# MB_audio.net
KiCad netlist of a schematic drawn in Altium Designer
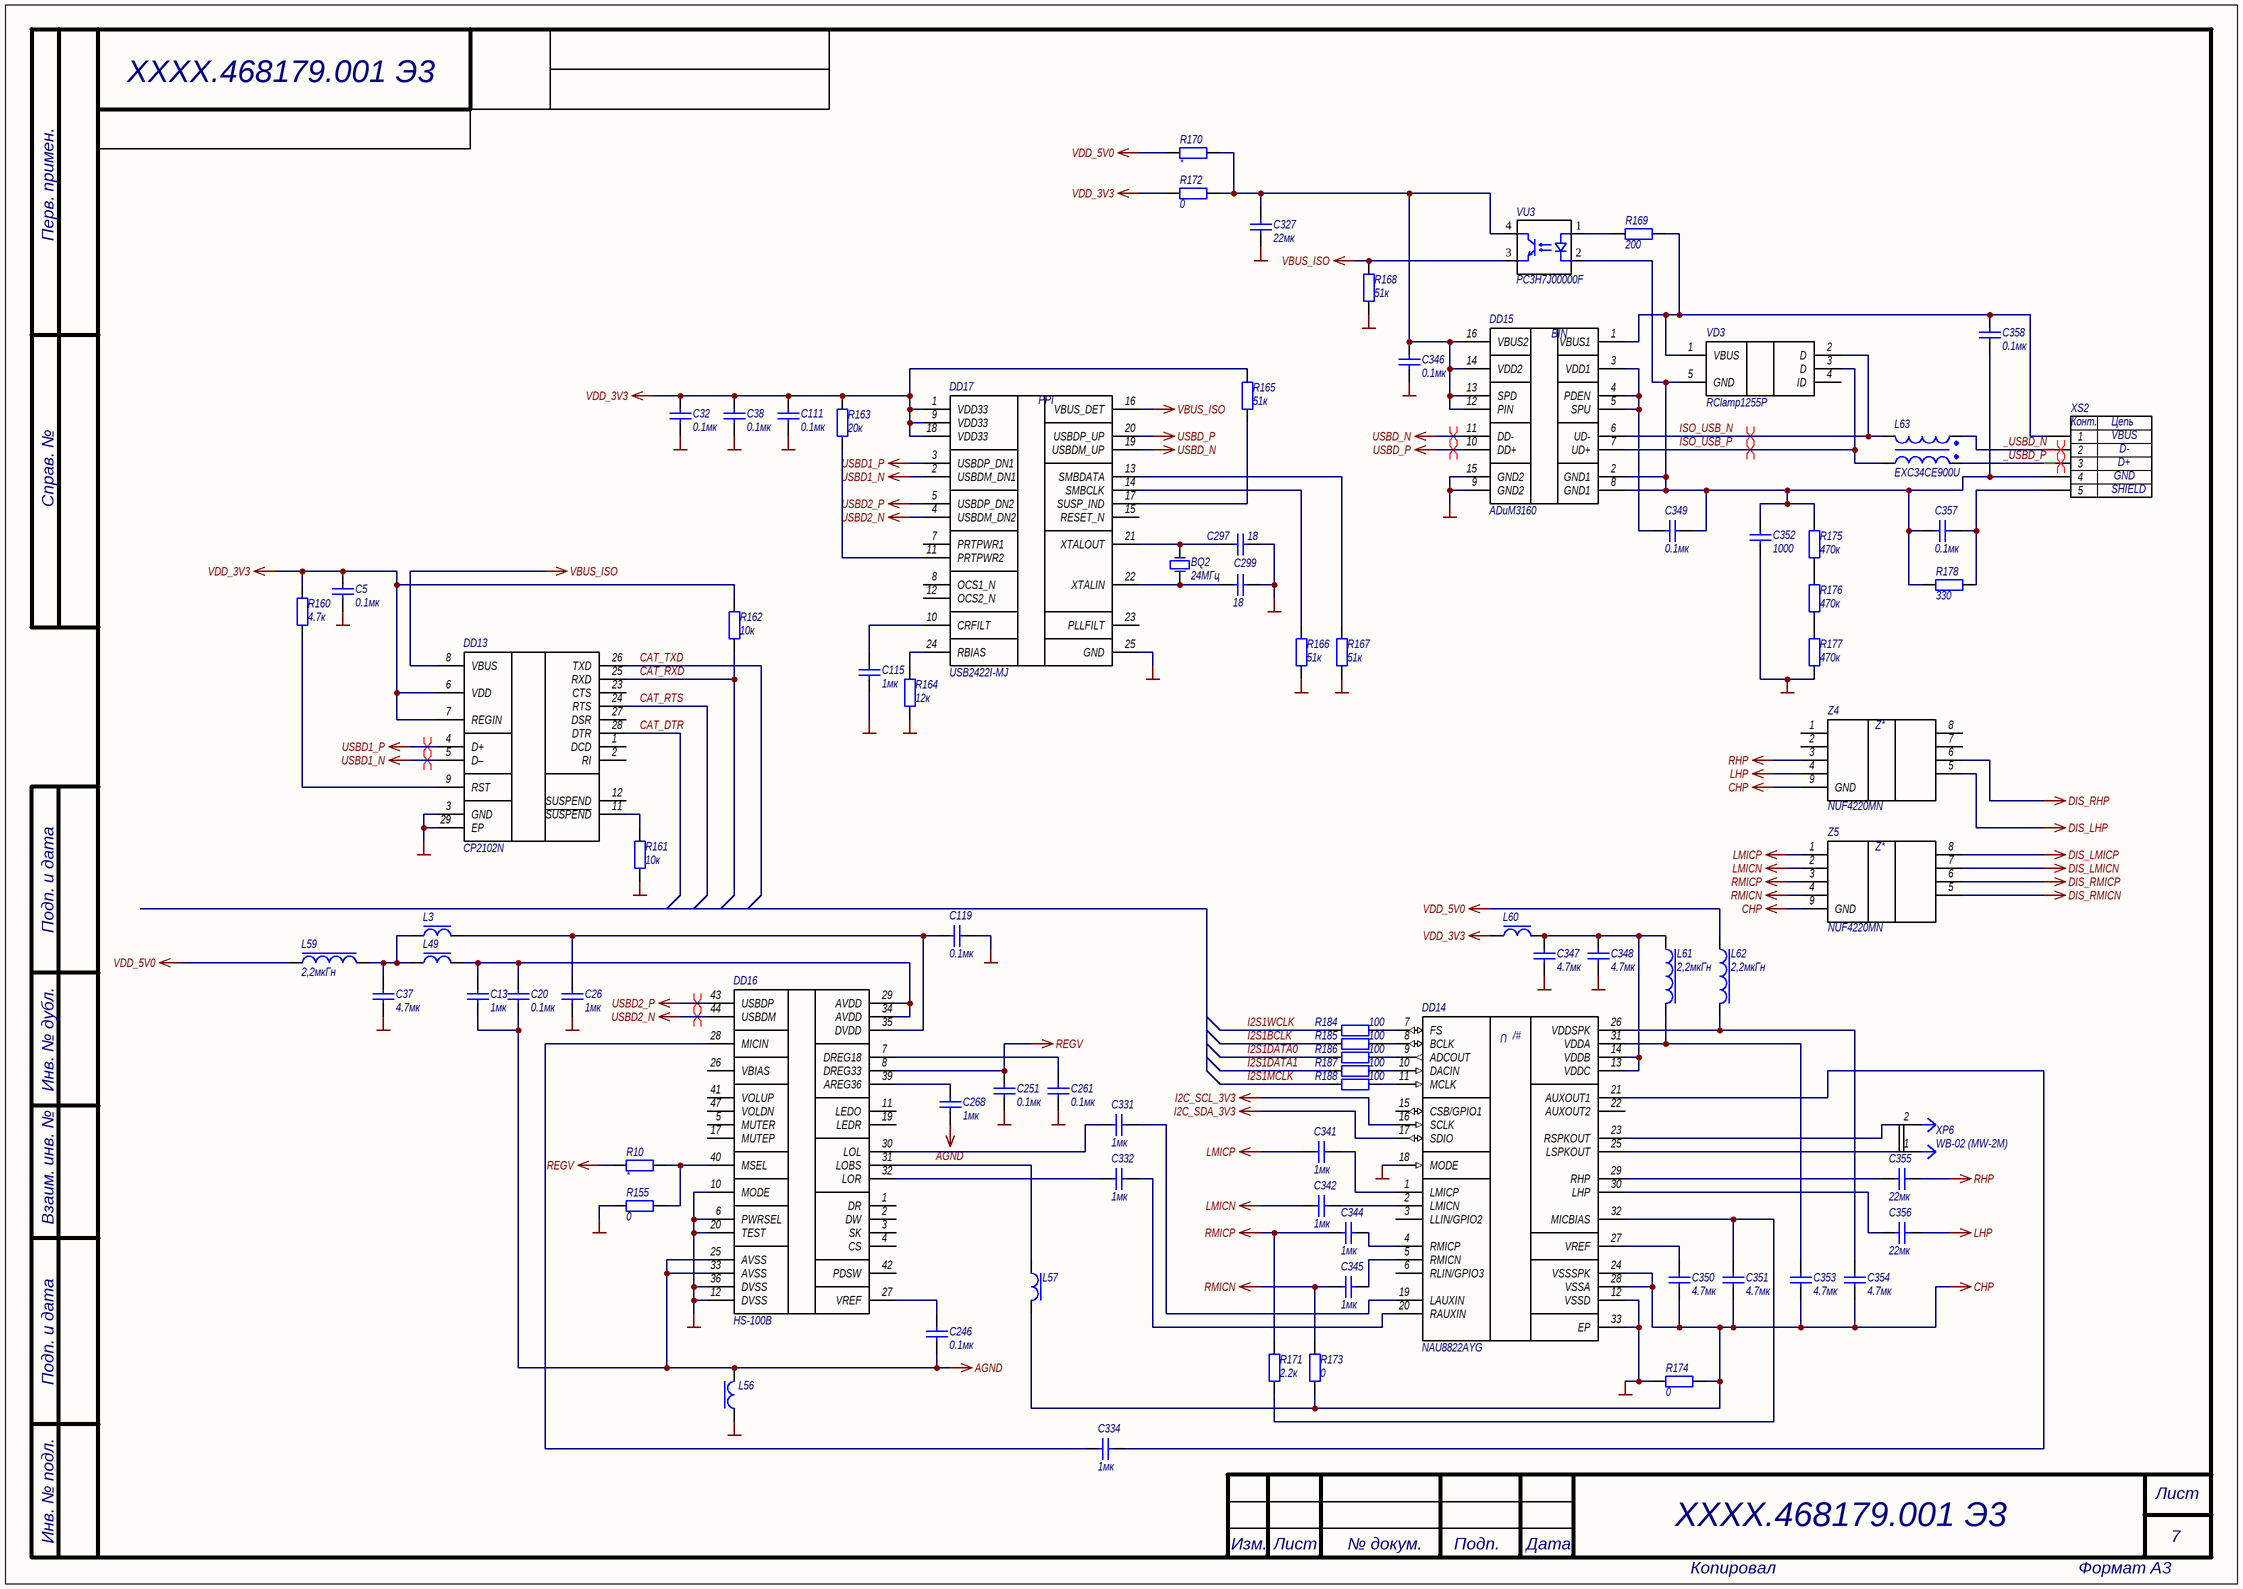
[diagram p0: MB_audio.SchDoc]

(export (version "E")
  (design (tool "Eeschema 10.0.6"))
  (components
    (comp (ref "BQ2")
      (value "24МГц")
      (footprint "ABRACOM ABM10")
      (description "Резонатор кварцевый")
      (fields (field (name "TOLERANCE") "±50 ppm") (field (name "MANUFACTURER") "ABRACON"))
      (libsource (lib "nels_other") (part "Кварц ABM10AIG-24.000MHZ-4Z-T3"))
    )
    (comp (ref "C5")
      (value "0.1мк")
      (footprint "CAPC1005X06N")
      (description "Кер. ЧИП-конденсатор")
      (fields (field (name "TOLERANCE") "±10%"))
      (libsource (lib "nels") (part "Кер.ЧИП конд. 0402 0.1мкФ X7R 10%, 16В"))
    )
    (comp (ref "C13")
      (value "1мк")
      (footprint "CAPC1005X06N")
      (description "Кер. ЧИП-конденсатор")
      (fields (field (name "TOLERANCE") "±10%"))
      (libsource (lib "nels_caps") (part "Кер.ЧИП конд. 0402 1мкФ X5R 10%, 10В"))
    )
    (comp (ref "C20")
      (value "0.1мк")
      (footprint "CAPC1005X06N")
      (description "Кер. ЧИП-конденсатор")
      (fields (field (name "TOLERANCE") "±10%"))
      (libsource (lib "nels") (part "Кер.ЧИП конд. 0402 0.1мкФ X7R 10%, 16В"))
    )
    (comp (ref "C26")
      (value "1мк")
      (footprint "CAPC1005X06N")
      (description "Кер. ЧИП-конденсатор")
      (fields (field (name "TOLERANCE") "±10%"))
      (libsource (lib "nels_caps") (part "Кер.ЧИП конд. 0402 1мкФ X5R 10%, 10В"))
    )
    (comp (ref "C32")
      (value "0.1мк")
      (footprint "CAPC1005X06N")
      (description "Кер. ЧИП-конденсатор")
      (fields (field (name "TOLERANCE") "±10%"))
      (libsource (lib "nels") (part "Кер.ЧИП конд. 0402 0.1мкФ X7R 10%, 16В"))
    )
    (comp (ref "C37")
      (value "4.7мк")
      (footprint "CAPC2012X12L")
      (description "Кер. ЧИП-конденсатор")
      (fields (field (name "TOLERANCE") "±20%") (field (name "MANUFACTURER") "Murata"))
      (libsource (lib "nels_caps") (part "Кер.ЧИП конд. 0805 4,7мкФ X5R 20% 16В"))
    )
    (comp (ref "C38")
      (value "0.1мк")
      (footprint "CAPC1005X06N")
      (description "Кер. ЧИП-конденсатор")
      (fields (field (name "TOLERANCE") "±10%"))
      (libsource (lib "nels") (part "Кер.ЧИП конд. 0402 0.1мкФ X7R 10%, 16В"))
    )
    (comp (ref "C111")
      (value "0.1мк")
      (footprint "CAPC1005X06N")
      (description "Кер. ЧИП-конденсатор")
      (fields (field (name "TOLERANCE") "±10%"))
      (libsource (lib "nels") (part "Кер.ЧИП конд. 0402 0.1мкФ X7R 10%, 16В"))
    )
    (comp (ref "C115")
      (value "1мк")
      (footprint "CAPC1005X06N")
      (description "Кер. ЧИП-конденсатор")
      (fields (field (name "TOLERANCE") "±10%"))
      (libsource (lib "nels_caps") (part "Кер.ЧИП конд. 0402 1мкФ X5R 10%, 10В"))
    )
    (comp (ref "C119")
      (value "0.1мк")
      (footprint "CAPC1005X06N")
      (description "Кер. ЧИП-конденсатор")
      (fields (field (name "TOLERANCE") "±10%"))
      (libsource (lib "nels") (part "Кер.ЧИП конд. 0402 0.1мкФ X7R 10%, 16В"))
    )
    (comp (ref "C246")
      (value "0.1мк")
      (footprint "CAPC1005X06N")
      (description "Кер. ЧИП-конденсатор")
      (fields (field (name "TOLERANCE") "±10%"))
      (libsource (lib "nels") (part "Кер.ЧИП конд. 0402 0.1мкФ X7R 10%, 16В"))
    )
    (comp (ref "C251")
      (value "0.1мк")
      (footprint "CAPC1005X06N")
      (description "Кер. ЧИП-конденсатор")
      (fields (field (name "TOLERANCE") "±10%"))
      (libsource (lib "nels") (part "Кер.ЧИП конд. 0402 0.1мкФ X7R 10%, 16В"))
    )
    (comp (ref "C261")
      (value "0.1мк")
      (footprint "CAPC1005X06N")
      (description "Кер. ЧИП-конденсатор")
      (fields (field (name "TOLERANCE") "±10%"))
      (libsource (lib "nels") (part "Кер.ЧИП конд. 0402 0.1мкФ X7R 10%, 16В"))
    )
    (comp (ref "C268")
      (value "1мк")
      (footprint "CAPC1005X06N")
      (description "Кер. ЧИП-конденсатор")
      (fields (field (name "TOLERANCE") "±10%"))
      (libsource (lib "nels_caps") (part "Кер.ЧИП конд. 0402 1мкФ X5R 10%, 10В"))
    )
    (comp (ref "C297")
      (value "18")
      (footprint "CAPC1005X06N")
      (description "Кер. ЧИП-конденсатор")
      (fields (field (name "TOLERANCE") "±5%"))
      (libsource (lib "nels_caps") (part "Кер.ЧИП конд. 0402 18пФ NPO 5%, 50В"))
    )
    (comp (ref "C299")
      (value "18")
      (footprint "CAPC1005X06N")
      (description "Кер. ЧИП-конденсатор")
      (fields (field (name "TOLERANCE") "±5%"))
      (libsource (lib "nels_caps") (part "Кер.ЧИП конд. 0402 18пФ NPO 5%, 50В"))
    )
    (comp (ref "C327")
      (value "22мк")
      (footprint "CAPC2012X12L")
      (description "Кер. ЧИП-конденсатор")
      (fields (field (name "MANUFACTURER") "TDK") (field (name "TOLERANCE") "±10%"))
      (libsource (lib "nels_caps") (part "Кер.ЧИП конд. 0805 22мкФ X5R 10% 16В"))
    )
    (comp (ref "C331")
      (value "1мк")
      (footprint "CAPC1005X06N")
      (description "Кер. ЧИП-конденсатор")
      (fields (field (name "TOLERANCE") "±10%"))
      (libsource (lib "nels_caps") (part "Кер.ЧИП конд. 0402 1мкФ X5R 10%, 10В"))
    )
    (comp (ref "C332")
      (value "1мк")
      (footprint "CAPC1005X06N")
      (description "Кер. ЧИП-конденсатор")
      (fields (field (name "TOLERANCE") "±10%"))
      (libsource (lib "nels_caps") (part "Кер.ЧИП конд. 0402 1мкФ X5R 10%, 10В"))
    )
    (comp (ref "C334")
      (value "1мк")
      (footprint "CAPC1005X06N")
      (description "Кер. ЧИП-конденсатор")
      (fields (field (name "TOLERANCE") "±10%"))
      (libsource (lib "nels_caps") (part "Кер.ЧИП конд. 0402 1мкФ X5R 10%, 10В"))
    )
    (comp (ref "C341")
      (value "1мк")
      (footprint "CAPC1005X06N")
      (description "Кер. ЧИП-конденсатор")
      (fields (field (name "TOLERANCE") "±10%"))
      (libsource (lib "nels_caps") (part "Кер.ЧИП конд. 0402 1мкФ X5R 10%, 10В"))
    )
    (comp (ref "C342")
      (value "1мк")
      (footprint "CAPC1005X06N")
      (description "Кер. ЧИП-конденсатор")
      (fields (field (name "TOLERANCE") "±10%"))
      (libsource (lib "nels_caps") (part "Кер.ЧИП конд. 0402 1мкФ X5R 10%, 10В"))
    )
    (comp (ref "C344")
      (value "1мк")
      (footprint "CAPC1005X06N")
      (description "Кер. ЧИП-конденсатор")
      (fields (field (name "TOLERANCE") "±10%"))
      (libsource (lib "nels_caps") (part "Кер.ЧИП конд. 0402 1мкФ X5R 10%, 10В"))
    )
    (comp (ref "C345")
      (value "1мк")
      (footprint "CAPC1005X06N")
      (description "Кер. ЧИП-конденсатор")
      (fields (field (name "TOLERANCE") "±10%"))
      (libsource (lib "nels_caps") (part "Кер.ЧИП конд. 0402 1мкФ X5R 10%, 10В"))
    )
    (comp (ref "C346")
      (value "0.1мк")
      (footprint "CAPC1005X06N")
      (description "Кер. ЧИП-конденсатор")
      (fields (field (name "TOLERANCE") "±10%"))
      (libsource (lib "nels") (part "Кер.ЧИП конд. 0402 0.1мкФ X7R 10%, 16В"))
    )
    (comp (ref "C347")
      (value "4.7мк")
      (footprint "CAPC2012X12L")
      (description "Кер. ЧИП-конденсатор")
      (fields (field (name "TOLERANCE") "±20%") (field (name "MANUFACTURER") "Murata"))
      (libsource (lib "nels_caps") (part "Кер.ЧИП конд. 0805 4,7мкФ X5R 20% 16В"))
    )
    (comp (ref "C348")
      (value "4.7мк")
      (footprint "CAPC2012X12L")
      (description "Кер. ЧИП-конденсатор")
      (fields (field (name "TOLERANCE") "±20%") (field (name "MANUFACTURER") "Murata"))
      (libsource (lib "nels_caps") (part "Кер.ЧИП конд. 0805 4,7мкФ X5R 20% 16В"))
    )
    (comp (ref "C349")
      (value "0.1мк")
      (footprint "CAPC1608X08L")
      (description "Кер. ЧИП-конденсатор")
      (fields (field (name "TOLERANCE") "±10%") (field (name "MANUFACTURER") "Murata"))
      (libsource (lib "nels_caps") (part "Кер.ЧИП конд. 0603 0.1мкФ X7R 10% 50В"))
    )
    (comp (ref "C350")
      (value "4.7мк")
      (footprint "CAPC2012X12L")
      (description "Кер. ЧИП-конденсатор")
      (fields (field (name "TOLERANCE") "±20%") (field (name "MANUFACTURER") "Murata"))
      (libsource (lib "nels_caps") (part "Кер.ЧИП конд. 0805 4,7мкФ X5R 20% 16В"))
    )
    (comp (ref "C351")
      (value "4.7мк")
      (footprint "CAPC2012X12L")
      (description "Кер. ЧИП-конденсатор")
      (fields (field (name "TOLERANCE") "±20%") (field (name "MANUFACTURER") "Murata"))
      (libsource (lib "nels_caps") (part "Кер.ЧИП конд. 0805 4,7мкФ X5R 20% 16В"))
    )
    (comp (ref "C352")
      (value "1000")
      (footprint "CAPRD7.5-9x5")
      (description "Защищенные конденсаторы 1000pF 250Vrms 20% L/S=10mm Bulk long")
      (fields
        (field (name "MANUFACTURER") "MURATA")
        (field (name "TOLERANCE") "±10%")
        (field (name "PUBLISHER") "Altium Limited")
      )
      (libsource (lib "nels_caps") (part "Конденсатор керамический защищенный 1000pF 250V AC (DE1E3KX102MA4BN01F)"))
    )
    (comp (ref "C353")
      (value "4.7мк")
      (footprint "CAPC2012X12L")
      (description "Кер. ЧИП-конденсатор")
      (fields (field (name "TOLERANCE") "±20%") (field (name "MANUFACTURER") "Murata"))
      (libsource (lib "nels_caps") (part "Кер.ЧИП конд. 0805 4,7мкФ X5R 20% 16В"))
    )
    (comp (ref "C354")
      (value "4.7мк")
      (footprint "CAPC2012X12L")
      (description "Кер. ЧИП-конденсатор")
      (fields (field (name "TOLERANCE") "±20%") (field (name "MANUFACTURER") "Murata"))
      (libsource (lib "nels_caps") (part "Кер.ЧИП конд. 0805 4,7мкФ X5R 20% 16В"))
    )
    (comp (ref "C355")
      (value "22мк")
      (footprint "CAPC2012X12L")
      (description "Кер. ЧИП-конденсатор")
      (fields (field (name "TOLERANCE") "±10%") (field (name "MANUFACTURER") "TDK"))
      (libsource (lib "nels_caps") (part "Кер.ЧИП конд. 0805 22мкФ X5R 10% 16В"))
    )
    (comp (ref "C356")
      (value "22мк")
      (footprint "CAPC2012X12L")
      (description "Кер. ЧИП-конденсатор")
      (fields (field (name "TOLERANCE") "±10%") (field (name "MANUFACTURER") "TDK"))
      (libsource (lib "nels_caps") (part "Кер.ЧИП конд. 0805 22мкФ X5R 10% 16В"))
    )
    (comp (ref "C357")
      (value "0.1мк")
      (footprint "CAPC1608X08L")
      (description "Кер. ЧИП-конденсатор")
      (fields (field (name "TOLERANCE") "±10%") (field (name "MANUFACTURER") "Murata"))
      (libsource (lib "nels_caps") (part "Кер.ЧИП конд. 0603 0.1мкФ X7R 10% 50В"))
    )
    (comp (ref "C358")
      (value "0.1мк")
      (footprint "CAPC1608X08L")
      (description "Кер. ЧИП-конденсатор")
      (fields (field (name "TOLERANCE") "±10%") (field (name "MANUFACTURER") "Murata"))
      (libsource (lib "nels_caps") (part "Кер.ЧИП конд. 0603 0.1мкФ X7R 10% 50В"))
    )
    (comp (ref "DD13")
      (value "CP2102N")
      (footprint "QFN50P500X500X80_HS-29N")
      (description "Single-Chip USB-to-UART Data Transfer")
      (fields (field (name "MANUFACTURER") "Silicon Labs"))
      (libsource (lib "nels_chip") (part "Микросхема CP2102N-A02-GQFN28"))
    )
    (comp (ref "DD14")
      (value "NAU8822AYG")
      (footprint "QFN50P500X500X100_HS-33L")
      (description "24-bit Stereo Audio Codec with Speaker Driver")
      (fields (field (name "MANUFACTURER") "NUVOTON"))
      (libsource (lib "nels_chip") (part "Микросхема NAU8822AYG"))
    )
    (comp (ref "DD15")
      (value "ADuM3160")
      (footprint "SOIC127P1030X265-16N")
      (description "Full/Low Speed 2.5 kV USB Digital Isolator")
      (fields (field (name "MANUFACTURER") "AD"))
      (libsource (lib "nels_chip") (part "Микросхема ADuM3160"))
    )
    (comp (ref "DD16")
      (value "HS-100B")
      (footprint "TSQFP50P900X900X160-48N")
      (description "A Highly Integrated USB Audio Single Chip")
      (fields (field (name "MANUFACTURER") "Cmedia"))
      (libsource (lib "MB") (part "Микросхема HS-100B"))
    )
    (comp (ref "DD17")
      (value "USB2422I-MJ")
      (footprint "QFN50P400X400X80_HS-25L")
      (description "2-Port USB 2.0 Hi-Speed Hub Controller")
      (fields (field (name "MANUFACTURER") "Microchip"))
      (libsource (lib "nels_chip") (part "Микросхема USB2422I-MJ"))
    )
    (comp (ref "L3")
      (value "BLM18PG121SN1D")
      (footprint "INDC1608X08L")
      (description "SMD EMI Suppression Filter EMIFIL")
      (fields (field (name "MANUFACTURER") "Murata"))
      (libsource (lib "nels_ind") (part "ЧИП дроссель 0603 BLM18PG121SN1D"))
    )
    (comp (ref "L49")
      (value "BLM18PG121SN1D")
      (footprint "INDC1608X08L")
      (description "SMD EMI Suppression Filter EMIFIL")
      (fields (field (name "MANUFACTURER") "Murata"))
      (libsource (lib "nels_ind") (part "ЧИП дроссель 0603 BLM18PG121SN1D"))
    )
    (comp (ref "L56")
      (value "BLM18PG121SN1D")
      (footprint "INDC1608X08L")
      (description "SMD EMI Suppression Filter EMIFIL")
      (fields (field (name "MANUFACTURER") "Murata"))
      (libsource (lib "nels_ind") (part "ЧИП дроссель 0603 BLM18PG121SN1D"))
    )
    (comp (ref "L57")
      (value "BLM18PG121SN1D")
      (footprint "INDC1608X08L")
      (description "SMD EMI Suppression Filter EMIFIL")
      (fields (field (name "MANUFACTURER") "Murata"))
      (libsource (lib "nels_ind") (part "ЧИП дроссель 0603 BLM18PG121SN1D"))
    )
    (comp (ref "L59")
      (value "2,2мкГн")
      (footprint "CSAB0420")
      (description "Molding Power Choke")
      (fields
        (field (name "MANUFACTURER") "Vishay")
        (field (name "MANUFACTURERPARTNUMBER") "IHLP1616ABER1R0M11")
      )
      (libsource (lib "nels_ind") (part "ЧИП индуктивность CSAB0420-2R2M"))
    )
    (comp (ref "L60")
      (value "BLM18PG121SN1D")
      (footprint "INDC1608X08L")
      (description "SMD EMI Suppression Filter EMIFIL")
      (fields (field (name "MANUFACTURER") "Murata"))
      (libsource (lib "nels_ind") (part "ЧИП дроссель 0603 BLM18PG121SN1D"))
    )
    (comp (ref "L61")
      (value "2,2мкГн")
      (footprint "CSAB0420")
      (description "Molding Power Choke")
      (fields
        (field (name "MANUFACTURER") "Vishay")
        (field (name "MANUFACTURERPARTNUMBER") "IHLP1616ABER1R0M11")
      )
      (libsource (lib "nels_ind") (part "ЧИП индуктивность CSAB0420-2R2M"))
    )
    (comp (ref "L62")
      (value "2,2мкГн")
      (footprint "CSAB0420")
      (description "Molding Power Choke")
      (fields
        (field (name "MANUFACTURER") "Vishay")
        (field (name "MANUFACTURERPARTNUMBER") "IHLP1616ABER1R0M11")
      )
      (libsource (lib "nels_ind") (part "ЧИП индуктивность CSAB0420-2R2M"))
    )
    (comp (ref "L63")
      (value "EXC34CE900U")
      (footprint "EXC34CE900U")
      (description "Common Mode Noise Filters EXC34CG/CE type")
      (fields (field (name "MANUFACTURER") "Panasonic"))
      (libsource (lib "nels_ind") (part "ЧИП синфазный фильтр 0805 EXC34CE900U"))
    )
    (comp (ref "R10")
      (value "*")
      (footprint "RESC1005X06N")
      (description "ЧИП-резистор")
      (fields (field (name "TOLERANCE") "±5%") (field (name "ALTIUM_VALUE") "*"))
      (libsource (lib "nels_res") (part "Чип резистор 0402 *"))
    )
    (comp (ref "R155")
      (value "0")
      (footprint "RESC1005X06N")
      (description "ЧИП-резистор")
      (fields (field (name "TOLERANCE") "±5%"))
      (libsource (lib "nels_res") (part "Чип резистор 0402 0 Ом"))
    )
    (comp (ref "R160")
      (value "4.7к")
      (footprint "RESC1005X06N")
      (description "ЧИП-резистор")
      (fields (field (name "TOLERANCE") "±5%"))
      (libsource (lib "nels_res") (part "Чип резистор 0402 4,7 кОм, 5%"))
    )
    (comp (ref "R161")
      (value "10к")
      (footprint "RESC1005X06N")
      (description "ЧИП-резистор")
      (fields (field (name "TOLERANCE") "±5%"))
      (libsource (lib "nels_res") (part "Чип резистор 0402 10 кОм, 5%"))
    )
    (comp (ref "R162")
      (value "10к")
      (footprint "RESC1005X06N")
      (description "ЧИП-резистор")
      (fields (field (name "TOLERANCE") "±5%"))
      (libsource (lib "nels_res") (part "Чип резистор 0402 10 кОм, 5%"))
    )
    (comp (ref "R163")
      (value "20к")
      (footprint "RESC1005X06N")
      (description "ЧИП-резистор")
      (fields (field (name "TOLERANCE") "±5%"))
      (libsource (lib "nels_res") (part "Чип резистор 0402 20 кОм, 5%"))
    )
    (comp (ref "R164")
      (value "12к")
      (footprint "RESC1005X06N")
      (description "ЧИП-резистор")
      (fields (field (name "TOLERANCE") "±5%"))
      (libsource (lib "nels_res") (part "Чип резистор 0402 12 кОм, 5%"))
    )
    (comp (ref "R165")
      (value "51к")
      (footprint "RESC1005X06N")
      (description "ЧИП-резистор")
      (fields (field (name "TOLERANCE") "±5%"))
      (libsource (lib "nels_res") (part "Чип резистор 0402 51 кОм, 5%"))
    )
    (comp (ref "R166")
      (value "51к")
      (footprint "RESC1005X06N")
      (description "ЧИП-резистор")
      (fields (field (name "TOLERANCE") "±5%"))
      (libsource (lib "nels_res") (part "Чип резистор 0402 51 кОм, 5%"))
    )
    (comp (ref "R167")
      (value "51к")
      (footprint "RESC1005X06N")
      (description "ЧИП-резистор")
      (fields (field (name "TOLERANCE") "±5%"))
      (libsource (lib "nels_res") (part "Чип резистор 0402 51 кОм, 5%"))
    )
    (comp (ref "R168")
      (value "51к")
      (footprint "RESC1005X06N")
      (description "ЧИП-резистор")
      (fields (field (name "TOLERANCE") "±5%"))
      (libsource (lib "nels_res") (part "Чип резистор 0402 51 кОм, 5%"))
    )
    (comp (ref "R169")
      (value "200")
      (footprint "RESC1005X06N")
      (description "ЧИП-резистор")
      (fields (field (name "TOLERANCE") "±5%"))
      (libsource (lib "nels_res") (part "Чип резистор 0402 200 Ом, 5%"))
    )
    (comp (ref "R170")
      (value "*")
      (footprint "RESC1005X06N")
      (description "ЧИП-резистор")
      (fields (field (name "TOLERANCE") "±5%") (field (name "ALTIUM_VALUE") "*"))
      (libsource (lib "nels_res") (part "Чип резистор 0402 *"))
    )
    (comp (ref "R171")
      (value "2.2к")
      (footprint "RESC1005X06N")
      (description "ЧИП-резистор")
      (fields (field (name "TOLERANCE") "±5%"))
      (libsource (lib "nels_res") (part "Чип резистор 0402 2,2 кОм, 5%"))
    )
    (comp (ref "R172")
      (value "0")
      (footprint "RESC1005X06N")
      (description "ЧИП-резистор")
      (fields (field (name "TOLERANCE") "±5%"))
      (libsource (lib "nels_res") (part "Чип резистор 0402 0 Ом"))
    )
    (comp (ref "R173")
      (value "0")
      (footprint "RESC1005X06N")
      (description "ЧИП-резистор")
      (fields (field (name "TOLERANCE") "±5%"))
      (libsource (lib "") (part "Чип резистор 0402 0 Ом_1"))
    )
    (comp (ref "R174")
      (value "0")
      (footprint "RESC1005X06N")
      (description "ЧИП-резистор")
      (fields (field (name "TOLERANCE") "±5%"))
      (libsource (lib "") (part "Чип резистор 0402 0 Ом_2"))
    )
    (comp (ref "R175")
      (value "470к")
      (footprint "RESC1005X06N")
      (description "ЧИП-резистор")
      (fields (field (name "TOLERANCE") "±5%"))
      (libsource (lib "nels_res") (part "Чип резистор 0402 470 кОм, 5%"))
    )
    (comp (ref "R176")
      (value "470к")
      (footprint "RESC1005X06N")
      (description "ЧИП-резистор")
      (fields (field (name "TOLERANCE") "±5%"))
      (libsource (lib "nels_res") (part "Чип резистор 0402 470 кОм, 5%"))
    )
    (comp (ref "R177")
      (value "470к")
      (footprint "RESC1005X06N")
      (description "ЧИП-резистор")
      (fields (field (name "TOLERANCE") "±5%"))
      (libsource (lib "nels_res") (part "Чип резистор 0402 470 кОм, 5%"))
    )
    (comp (ref "R178")
      (value "330")
      (footprint "RESC1005X06N")
      (description "ЧИП-резистор")
      (fields (field (name "TOLERANCE") "±5%"))
      (libsource (lib "nels_res") (part "Чип резистор 0402 330 Ом, 5%"))
    )
    (comp (ref "R184")
      (value "100")
      (footprint "RESC1005X06N")
      (description "ЧИП-резистор")
      (fields (field (name "TOLERANCE") "±5%"))
      (libsource (lib "nels_res") (part "Чип резистор 0402 100 Ом, 5%"))
    )
    (comp (ref "R185")
      (value "100")
      (footprint "RESC1005X06N")
      (description "ЧИП-резистор")
      (fields (field (name "TOLERANCE") "±5%"))
      (libsource (lib "nels_res") (part "Чип резистор 0402 100 Ом, 5%"))
    )
    (comp (ref "R186")
      (value "100")
      (footprint "RESC1005X06N")
      (description "ЧИП-резистор")
      (fields (field (name "TOLERANCE") "±5%"))
      (libsource (lib "nels_res") (part "Чип резистор 0402 100 Ом, 5%"))
    )
    (comp (ref "R187")
      (value "100")
      (footprint "RESC1005X06N")
      (description "ЧИП-резистор")
      (fields (field (name "TOLERANCE") "±5%"))
      (libsource (lib "nels_res") (part "Чип резистор 0402 100 Ом, 5%"))
    )
    (comp (ref "R188")
      (value "100")
      (footprint "RESC1005X06N")
      (description "ЧИП-резистор")
      (fields (field (name "TOLERANCE") "±5%"))
      (libsource (lib "nels_res") (part "Чип резистор 0402 100 Ом, 5%"))
    )
    (comp (ref "VD3")
      (value "RClamp1255P")
      (footprint "SLP2018P6")
      (description "Low Capacitance RClamp Surge Protection for uUSB Interfaces")
      (fields (field (name "MANUFACTURER") "SEMTECH"))
      (libsource (lib "nels_other") (part "Диодная сборка RClamp1255P"))
    )
    (comp (ref "VU3")
      (value "PC3H7J00000F")
      (footprint "SO4-170-1.27")
      (description "Mini-falt Package, General Purpose Half Pitch Photocouper")
      (libsource (lib "nels_other") (part "Оптопара транзисторная PC3H7J00000F"))
    )
    (comp (ref "XP6")
      (value "WB-02 (MW-2M)")
      (footprint "WB-02 (MW-2M) pitch 2.00mm")
      (description "Соединитель")
      (libsource (lib "nels_conn") (part "Соединитель WB-02 (MW-2M)"))
    )
    (comp (ref "XS2")
      (value "USBB-1J")
      (footprint "USB2.5-2H4D")
      (description "Universal Serial Bus (USB) Shielded I/O Receptacle, Right Angle, Type B")
      (fields (field (name "MANUFACTURER") "Connfly"))
      (libsource (lib "nels_conn") (part "Соединитель USBB-1J"))
    )
    (comp (ref "Z4")
      (value "NUF4220MN")
      (footprint "QFN50P200X200X80_HS-9L")
      (description "ESD/EMI Protection  for Audio Interfaces")
      (fields (field (name "MANUFACTURER") "onsemi"))
      (libsource (lib "nels_other") (part "Фильтр EMI NUF4220MN"))
    )
    (comp (ref "Z5")
      (value "NUF4220MN")
      (footprint "QFN50P200X200X80_HS-9L")
      (description "ESD/EMI Protection  for Audio Interfaces")
      (fields (field (name "MANUFACTURER") "onsemi"))
      (libsource (lib "nels_other") (part "Фильтр EMI NUF4220MN"))
    )
  )
  (nets
    (net (code "1") (name "/CAT_DTR") (class "Default")
      (node (ref "DD13") (pin "28") (pinfunction "DTR_28") (pintype "passive"))
    )
    (net (code "2") (name "/CAT_RTS") (class "Default")
      (node (ref "DD13") (pin "24") (pinfunction "RTS_24") (pintype "passive"))
    )
    (net (code "3") (name "/CAT_RXD") (class "Default")
      (node (ref "DD13") (pin "25") (pinfunction "RXD_25") (pintype "passive"))
      (node (ref "R162") (pin "1") (pinfunction "1_1") (pintype "passive"))
    )
    (net (code "4") (name "/CAT_TXD") (class "Default")
      (node (ref "DD13") (pin "26") (pinfunction "TXD_26") (pintype "passive"))
    )
    (net (code "5") (name "/I2S1BCLK") (class "Default")
      (node (ref "R185") (pin "1") (pinfunction "1_1") (pintype "passive"))
    )
    (net (code "6") (name "/I2S1DATA0") (class "Default")
      (node (ref "R186") (pin "1") (pinfunction "1_1") (pintype "passive"))
    )
    (net (code "7") (name "/I2S1DATA1") (class "Default")
      (node (ref "R187") (pin "1") (pinfunction "1_1") (pintype "passive"))
    )
    (net (code "8") (name "/I2S1MCLK") (class "Default")
      (node (ref "R188") (pin "1") (pinfunction "1_1") (pintype "passive"))
    )
    (net (code "9") (name "/I2S1WCLK") (class "Default")
      (node (ref "R184") (pin "1") (pinfunction "1_1") (pintype "passive"))
    )
    (net (code "10") (name "/ISO_USB_N") (class "Default")
      (node (ref "DD15") (pin "6") (pinfunction "UD-_6") (pintype "passive"))
      (node (ref "L63") (pin "2") (pinfunction "2_2") (pintype "passive"))
      (node (ref "VD3") (pin "2") (pinfunction "D_2") (pintype "passive"))
    )
    (net (code "11") (name "/ISO_USB_P") (class "Default")
      (node (ref "DD15") (pin "7") (pinfunction "UD+_7") (pintype "passive"))
      (node (ref "L63") (pin "3") (pinfunction "3_3") (pintype "passive"))
      (node (ref "VD3") (pin "3") (pinfunction "D_3") (pintype "passive"))
    )
    (net (code "12") (name "/_USBD_N") (class "Default")
      (node (ref "L63") (pin "1") (pinfunction "1_1") (pintype "passive"))
      (node (ref "XS2") (pin "2") (pinfunction "2_2") (pintype "passive"))
    )
    (net (code "13") (name "/_USBD_P") (class "Default")
      (node (ref "L63") (pin "4") (pinfunction "4_4") (pintype "passive"))
      (node (ref "XS2") (pin "3") (pinfunction "3_3") (pintype "passive"))
    )
    (net (code "14") (name "AGND") (class "Default")
      (node (ref "C13") (pin "1") (pinfunction "1_1") (pintype "passive"))
      (node (ref "C20") (pin "1") (pinfunction "1_1") (pintype "passive"))
      (node (ref "C246") (pin "1") (pinfunction "1_1") (pintype "passive"))
      (node (ref "C268") (pin "1") (pinfunction "1_1") (pintype "passive"))
      (node (ref "DD16") (pin "25") (pinfunction "AVSS_25") (pintype "passive"))
      (node (ref "DD16") (pin "33") (pinfunction "AVSS_33") (pintype "passive"))
      (node (ref "L56") (pin "2") (pinfunction "2_2") (pintype "passive"))
    )
    (net (code "15") (name "CHP") (class "Default")
      (node (ref "C350") (pin "2") (pinfunction "2_2") (pintype "passive"))
      (node (ref "C351") (pin "2") (pinfunction "2_2") (pintype "passive"))
      (node (ref "C353") (pin "2") (pinfunction "2_2") (pintype "passive"))
      (node (ref "C354") (pin "2") (pinfunction "2_2") (pintype "passive"))
      (node (ref "DD14") (pin "24") (pinfunction "VSSSPK_24") (pintype "power_in"))
      (node (ref "DD14") (pin "28") (pinfunction "VSSA_28") (pintype "power_in"))
      (node (ref "L57") (pin "2") (pinfunction "2_2") (pintype "passive"))
      (node (ref "R173") (pin "1") (pinfunction "1_1") (pintype "passive"))
      (node (ref "R174") (pin "2") (pinfunction "2_2") (pintype "passive"))
      (node (ref "Z4") (pin "9") (pinfunction "GND_9") (pintype "passive"))
      (node (ref "Z5") (pin "9") (pinfunction "GND_9") (pintype "passive"))
    )
    (net (code "16") (name "DIS_LHP") (class "Default") (node (ref "Z4") (pin "5") (pintype "passive")))
    (net (code "17") (name "DIS_LMICN") (class "Default") (node (ref "Z5") (pin "7") (pintype "passive")))
    (net (code "18") (name "DIS_LMICP") (class "Default") (node (ref "Z5") (pin "8") (pintype "passive")))
    (net (code "19") (name "DIS_RHP") (class "Default") (node (ref "Z4") (pin "6") (pintype "passive")))
    (net (code "20") (name "DIS_RMICN") (class "Default") (node (ref "Z5") (pin "5") (pintype "passive")))
    (net (code "21") (name "DIS_RMICP") (class "Default") (node (ref "Z5") (pin "6") (pintype "passive")))
    (net (code "22") (name "GND") (class "Default")
      (node (ref "C111") (pin "1") (pinfunction "1_1") (pintype "passive"))
      (node (ref "C115") (pin "1") (pinfunction "1_1") (pintype "passive"))
      (node (ref "C119") (pin "1") (pinfunction "1_1") (pintype "passive"))
      (node (ref "C251") (pin "1") (pinfunction "1_1") (pintype "passive"))
      (node (ref "C26") (pin "2") (pinfunction "2_2") (pintype "passive"))
      (node (ref "C261") (pin "1") (pinfunction "1_1") (pintype "passive"))
      (node (ref "C297") (pin "2") (pinfunction "2_2") (pintype "passive"))
      (node (ref "C299") (pin "2") (pinfunction "2_2") (pintype "passive"))
      (node (ref "C32") (pin "1") (pinfunction "1_1") (pintype "passive"))
      (node (ref "C327") (pin "1") (pinfunction "1_1") (pintype "passive"))
      (node (ref "C346") (pin "1") (pinfunction "1_1") (pintype "passive"))
      (node (ref "C347") (pin "2") (pinfunction "2_2") (pintype "passive"))
      (node (ref "C348") (pin "2") (pinfunction "2_2") (pintype "passive"))
      (node (ref "C352") (pin "2") (pinfunction "2_2") (pintype "passive"))
      (node (ref "C37") (pin "2") (pinfunction "2_2") (pintype "passive"))
      (node (ref "C38") (pin "1") (pinfunction "1_1") (pintype "passive"))
      (node (ref "C5") (pin "1") (pinfunction "1_1") (pintype "passive"))
      (node (ref "DD13") (pin "29") (pinfunction "EP_29") (pintype "passive"))
      (node (ref "DD13") (pin "3") (pinfunction "GND_3") (pintype "passive"))
      (node (ref "DD14") (pin "12") (pinfunction "VSSD_12") (pintype "power_in"))
      (node (ref "DD14") (pin "18") (pinfunction "MODE_18") (pintype "input"))
      (node (ref "DD14") (pin "33") (pinfunction "EP_33") (pintype "passive"))
      (node (ref "DD15") (pin "15") (pinfunction "GND2_15") (pintype "passive"))
      (node (ref "DD15") (pin "9") (pinfunction "GND2_9") (pintype "passive"))
      (node (ref "DD16") (pin "10") (pinfunction "MODE_10") (pintype "passive"))
      (node (ref "DD16") (pin "12") (pinfunction "DVSS_12") (pintype "passive"))
      (node (ref "DD16") (pin "20") (pinfunction "TEST_20") (pintype "passive"))
      (node (ref "DD16") (pin "36") (pinfunction "DVSS_36") (pintype "passive"))
      (node (ref "DD16") (pin "6") (pinfunction "PWRSEL_6") (pintype "passive"))
      (node (ref "DD17") (pin "25") (pinfunction "GND_25") (pintype "passive"))
      (node (ref "L56") (pin "1") (pinfunction "1_1") (pintype "passive"))
      (node (ref "R155") (pin "2") (pinfunction "2_2") (pintype "passive"))
      (node (ref "R161") (pin "1") (pinfunction "1_1") (pintype "passive"))
      (node (ref "R164") (pin "1") (pinfunction "1_1") (pintype "passive"))
      (node (ref "R166") (pin "1") (pinfunction "1_1") (pintype "passive"))
      (node (ref "R167") (pin "1") (pinfunction "1_1") (pintype "passive"))
      (node (ref "R168") (pin "1") (pinfunction "1_1") (pintype "passive"))
      (node (ref "R174") (pin "1") (pinfunction "1_1") (pintype "passive"))
      (node (ref "R177") (pin "1") (pinfunction "1_1") (pintype "passive"))
    )
    (net (code "23") (name "I2C_SCL_3V3") (class "Default")
      (node (ref "DD14") (pin "16") (pinfunction "SCLK_16") (pintype "input"))
    )
    (net (code "24") (name "I2C_SDA_3V3") (class "Default")
      (node (ref "DD14") (pin "17") (pinfunction "SDIO_17") (pintype "bidirectional"))
    )
    (net (code "25") (name "LHP") (class "Default")
      (node (ref "C356") (pin "1") (pinfunction "1_1") (pintype "passive"))
      (node (ref "Z4") (pin "4") (pintype "passive"))
    )
    (net (code "26") (name "LMICN") (class "Default")
      (node (ref "C342") (pin "1") (pinfunction "1_1") (pintype "passive"))
      (node (ref "Z5") (pin "2") (pintype "passive"))
    )
    (net (code "27") (name "LMICP") (class "Default")
      (node (ref "C341") (pin "1") (pinfunction "1_1") (pintype "passive"))
      (node (ref "Z5") (pin "1") (pintype "passive"))
    )
    (net (code "28") (name "Net-(BQ2-OSC1)") (class "Default")
      (node (ref "BQ2") (pin "1") (pinfunction "OSC1_1") (pintype "passive"))
      (node (ref "C297") (pin "1") (pinfunction "1_1") (pintype "passive"))
      (node (ref "DD17") (pin "21") (pinfunction "XTALOUT_21") (pintype "passive"))
    )
    (net (code "29") (name "Net-(BQ2-OSC2)") (class "Default")
      (node (ref "BQ2") (pin "3") (pinfunction "OSC2_3") (pintype "passive"))
      (node (ref "C299") (pin "1") (pinfunction "1_1") (pintype "passive"))
      (node (ref "DD17") (pin "22") (pinfunction "XTALIN_22") (pintype "passive"))
    )
    (net (code "30") (name "Net-(C13-Pad2)") (class "Default")
      (node (ref "C13") (pin "2") (pinfunction "2_2") (pintype "passive"))
      (node (ref "C20") (pin "2") (pinfunction "2_2") (pintype "passive"))
      (node (ref "DD16") (pin "29") (pinfunction "AVDD_29") (pintype "passive"))
      (node (ref "DD16") (pin "34") (pinfunction "AVDD_34") (pintype "passive"))
      (node (ref "L49") (pin "2") (pinfunction "2_2") (pintype "passive"))
    )
    (net (code "31") (name "Net-(C37-Pad1)") (class "Default")
      (node (ref "C37") (pin "1") (pinfunction "1_1") (pintype "passive"))
      (node (ref "L3") (pin "1") (pinfunction "1_1") (pintype "passive"))
      (node (ref "L49") (pin "1") (pinfunction "1_1") (pintype "passive"))
      (node (ref "L59") (pin "2") (pinfunction "2_2") (pintype "passive"))
    )
    (net (code "32") (name "Net-(C357-Pad1)") (class "Default")
      (node (ref "C357") (pin "1") (pinfunction "1_1") (pintype "passive"))
      (node (ref "R178") (pin "1") (pinfunction "1_1") (pintype "passive"))
      (node (ref "XS2") (pin "5") (pinfunction "5_5") (pintype "passive"))
    )
    (net (code "33") (name "Net-(DD13-RST)") (class "Default")
      (node (ref "DD13") (pin "9") (pinfunction "RST_9") (pintype "passive"))
      (node (ref "R160") (pin "1") (pinfunction "1_1") (pintype "passive"))
    )
    (net (code "34") (name "Net-(DD13-~{SUSPEND})") (class "Default")
      (node (ref "DD13") (pin "11") (pinfunction "~{SUSPEND}_11") (pintype "passive"))
      (node (ref "R161") (pin "2") (pinfunction "2_2") (pintype "passive"))
    )
    (net (code "35") (name "Net-(DD14-ADCOUT)") (class "Default")
      (node (ref "DD14") (pin "9") (pinfunction "ADCOUT_9") (pintype "output"))
      (node (ref "R186") (pin "2") (pinfunction "2_2") (pintype "passive"))
    )
    (net (code "36") (name "Net-(DD14-AUXOUT1)") (class "Default")
      (node (ref "C334") (pin "2") (pinfunction "2_2") (pintype "passive"))
      (node (ref "DD14") (pin "21") (pinfunction "AUXOUT1_21") (pintype "passive"))
    )
    (net (code "37") (name "Net-(DD14-BCLK)") (class "Default")
      (node (ref "DD14") (pin "8") (pinfunction "BCLK_8") (pintype "bidirectional"))
      (node (ref "R185") (pin "2") (pinfunction "2_2") (pintype "passive"))
    )
    (net (code "38") (name "Net-(DD14-DACIN)") (class "Default")
      (node (ref "DD14") (pin "10") (pinfunction "DACIN_10") (pintype "input"))
      (node (ref "R187") (pin "2") (pinfunction "2_2") (pintype "passive"))
    )
    (net (code "39") (name "Net-(DD14-FS)") (class "Default")
      (node (ref "DD14") (pin "7") (pinfunction "FS_7") (pintype "bidirectional"))
      (node (ref "R184") (pin "2") (pinfunction "2_2") (pintype "passive"))
    )
    (net (code "40") (name "Net-(DD14-LAUXIN)") (class "Default")
      (node (ref "C331") (pin "2") (pinfunction "2_2") (pintype "passive"))
      (node (ref "DD14") (pin "19") (pinfunction "LAUXIN_19") (pintype "passive"))
    )
    (net (code "41") (name "Net-(DD14-LHP)") (class "Default")
      (node (ref "C356") (pin "2") (pinfunction "2_2") (pintype "passive"))
      (node (ref "DD14") (pin "30") (pinfunction "LHP_30") (pintype "passive"))
    )
    (net (code "42") (name "Net-(DD14-LMICN)") (class "Default")
      (node (ref "C342") (pin "2") (pinfunction "2_2") (pintype "passive"))
      (node (ref "DD14") (pin "2") (pinfunction "LMICN_2") (pintype "passive"))
    )
    (net (code "43") (name "Net-(DD14-LMICP)") (class "Default")
      (node (ref "C341") (pin "2") (pinfunction "2_2") (pintype "passive"))
      (node (ref "DD14") (pin "1") (pinfunction "LMICP_1") (pintype "passive"))
    )
    (net (code "44") (name "Net-(DD14-LSPKOUT)") (class "Default")
      (node (ref "DD14") (pin "25") (pinfunction "LSPKOUT_25") (pintype "passive"))
      (node (ref "XP6") (pin "1") (pinfunction "~_1") (pintype "passive"))
    )
    (net (code "45") (name "Net-(DD14-MCLK)") (class "Default")
      (node (ref "DD14") (pin "11") (pinfunction "MCLK_11") (pintype "input"))
      (node (ref "R188") (pin "2") (pinfunction "2_2") (pintype "passive"))
    )
    (net (code "46") (name "Net-(DD14-MICBIAS)") (class "Default")
      (node (ref "C351") (pin "1") (pinfunction "1_1") (pintype "passive"))
      (node (ref "DD14") (pin "32") (pinfunction "MICBIAS_32") (pintype "passive"))
      (node (ref "R171") (pin "1") (pinfunction "1_1") (pintype "passive"))
    )
    (net (code "47") (name "Net-(DD14-RAUXIN)") (class "Default")
      (node (ref "C332") (pin "2") (pinfunction "2_2") (pintype "passive"))
      (node (ref "DD14") (pin "20") (pinfunction "RAUXIN_20") (pintype "passive"))
    )
    (net (code "48") (name "Net-(DD14-RHP)") (class "Default")
      (node (ref "C355") (pin "2") (pinfunction "2_2") (pintype "passive"))
      (node (ref "DD14") (pin "29") (pinfunction "RHP_29") (pintype "passive"))
    )
    (net (code "49") (name "Net-(DD14-RMICN)") (class "Default")
      (node (ref "C345") (pin "2") (pinfunction "2_2") (pintype "passive"))
      (node (ref "DD14") (pin "5") (pinfunction "RMICN_5") (pintype "passive"))
    )
    (net (code "50") (name "Net-(DD14-RMICP)") (class "Default")
      (node (ref "C344") (pin "2") (pinfunction "2_2") (pintype "passive"))
      (node (ref "DD14") (pin "4") (pinfunction "RMICP_4") (pintype "passive"))
    )
    (net (code "51") (name "Net-(DD14-RSPKOUT)") (class "Default")
      (node (ref "DD14") (pin "23") (pinfunction "RSPKOUT_23") (pintype "passive"))
      (node (ref "XP6") (pin "2") (pinfunction "~_2") (pintype "passive"))
    )
    (net (code "52") (name "Net-(DD14-VDDA)") (class "Default")
      (node (ref "C353") (pin "1") (pinfunction "1_1") (pintype "passive"))
      (node (ref "DD14") (pin "31") (pinfunction "VDDA_31") (pintype "power_in"))
      (node (ref "L61") (pin "2") (pinfunction "2_2") (pintype "passive"))
    )
    (net (code "53") (name "Net-(DD14-VDDB)") (class "Default")
      (node (ref "C347") (pin "1") (pinfunction "1_1") (pintype "passive"))
      (node (ref "C348") (pin "1") (pinfunction "1_1") (pintype "passive"))
      (node (ref "DD14") (pin "13") (pinfunction "VDDC_13") (pintype "power_in"))
      (node (ref "DD14") (pin "14") (pinfunction "VDDB_14") (pintype "power_in"))
      (node (ref "L60") (pin "2") (pinfunction "2_2") (pintype "passive"))
      (node (ref "L61") (pin "1") (pinfunction "1_1") (pintype "passive"))
    )
    (net (code "54") (name "Net-(DD14-VDDSPK)") (class "Default")
      (node (ref "C354") (pin "1") (pinfunction "1_1") (pintype "passive"))
      (node (ref "DD14") (pin "26") (pinfunction "VDDSPK_26") (pintype "power_in"))
      (node (ref "L62") (pin "2") (pinfunction "2_2") (pintype "passive"))
    )
    (net (code "55") (name "Net-(DD14-VREF)") (class "Default")
      (node (ref "C350") (pin "1") (pinfunction "1_1") (pintype "passive"))
      (node (ref "DD14") (pin "27") (pinfunction "VREF_27") (pintype "power_in"))
    )
    (net (code "56") (name "Net-(DD15-PDEN)") (class "Default")
      (node (ref "C349") (pin "2") (pinfunction "2_2") (pintype "passive"))
      (node (ref "DD15") (pin "3") (pinfunction "VDD1_3") (pintype "passive"))
      (node (ref "DD15") (pin "4") (pinfunction "PDEN_4") (pintype "passive"))
      (node (ref "DD15") (pin "5") (pinfunction "SPU_5") (pintype "passive"))
    )
    (net (code "57") (name "Net-(DD15-PIN)") (class "Default")
      (node (ref "C327") (pin "2") (pinfunction "2_2") (pintype "passive"))
      (node (ref "C346") (pin "2") (pinfunction "2_2") (pintype "passive"))
      (node (ref "DD15") (pin "12") (pinfunction "PIN_12") (pintype "passive"))
      (node (ref "DD15") (pin "13") (pinfunction "SPD_13") (pintype "passive"))
      (node (ref "DD15") (pin "14") (pinfunction "VDD2_14") (pintype "passive"))
      (node (ref "DD15") (pin "16") (pinfunction "VBUS2_16") (pintype "passive"))
      (node (ref "R170") (pin "1") (pinfunction "1_1") (pintype "passive"))
      (node (ref "R172") (pin "1") (pinfunction "1_1") (pintype "passive"))
      (node (ref "VU3") (pin "4") (pinfunction "C_4") (pintype "passive"))
    )
    (net (code "58") (name "Net-(DD15-VBUS1)") (class "Default")
      (node (ref "C358") (pin "2") (pinfunction "2_2") (pintype "passive"))
      (node (ref "DD15") (pin "1") (pinfunction "VBUS1_1") (pintype "passive"))
      (node (ref "R169") (pin "1") (pinfunction "1_1") (pintype "passive"))
      (node (ref "VD3") (pin "1") (pinfunction "VBUS_1") (pintype "passive"))
      (node (ref "XS2") (pin "1") (pinfunction "1_1") (pintype "passive"))
    )
    (net (code "59") (name "Net-(DD16-AREG36)") (class "Default")
      (node (ref "C268") (pin "2") (pinfunction "2_2") (pintype "passive"))
      (node (ref "DD16") (pin "39") (pinfunction "AREG36_39") (pintype "passive"))
    )
    (net (code "60") (name "Net-(DD16-DREG18)") (class "Default")
      (node (ref "C261") (pin "2") (pinfunction "2_2") (pintype "passive"))
      (node (ref "DD16") (pin "7") (pinfunction "DREG18_7") (pintype "passive"))
    )
    (net (code "61") (name "Net-(DD16-DVDD)") (class "Default")
      (node (ref "C119") (pin "2") (pinfunction "2_2") (pintype "passive"))
      (node (ref "C26") (pin "1") (pinfunction "1_1") (pintype "passive"))
      (node (ref "DD16") (pin "35") (pinfunction "DVDD_35") (pintype "passive"))
      (node (ref "L3") (pin "2") (pinfunction "2_2") (pintype "passive"))
    )
    (net (code "62") (name "Net-(DD16-LOBS)") (class "Default")
      (node (ref "DD16") (pin "31") (pinfunction "LOBS_31") (pintype "passive"))
      (node (ref "L57") (pin "1") (pinfunction "1_1") (pintype "passive"))
    )
    (net (code "63") (name "Net-(DD16-LOL)") (class "Default")
      (node (ref "C331") (pin "1") (pinfunction "1_1") (pintype "passive"))
      (node (ref "DD16") (pin "30") (pinfunction "LOL_30") (pintype "passive"))
    )
    (net (code "64") (name "Net-(DD16-LOR)") (class "Default")
      (node (ref "C332") (pin "1") (pinfunction "1_1") (pintype "passive"))
      (node (ref "DD16") (pin "32") (pinfunction "LOR_32") (pintype "passive"))
    )
    (net (code "65") (name "Net-(DD16-MICIN)") (class "Default")
      (node (ref "C334") (pin "1") (pinfunction "1_1") (pintype "passive"))
      (node (ref "DD16") (pin "28") (pinfunction "MICIN_28") (pintype "passive"))
    )
    (net (code "66") (name "Net-(DD16-MSEL)") (class "Default")
      (node (ref "DD16") (pin "40") (pinfunction "MSEL_40") (pintype "passive"))
      (node (ref "R10") (pin "1") (pinfunction "1_1") (pintype "passive"))
      (node (ref "R155") (pin "1") (pinfunction "1_1") (pintype "passive"))
    )
    (net (code "67") (name "Net-(DD16-VREF)") (class "Default")
      (node (ref "C246") (pin "2") (pinfunction "2_2") (pintype "passive"))
      (node (ref "DD16") (pin "27") (pinfunction "VREF_27") (pintype "passive"))
    )
    (net (code "68") (name "Net-(DD17-CRFILT)") (class "Default")
      (node (ref "C115") (pin "2") (pinfunction "2_2") (pintype "passive"))
      (node (ref "DD17") (pin "10") (pinfunction "CRFILT_10") (pintype "passive"))
    )
    (net (code "69") (name "Net-(DD17-PRTPWR2)") (class "Default")
      (node (ref "DD17") (pin "11") (pinfunction "PRTPWR2_11") (pintype "passive"))
      (node (ref "R163") (pin "1") (pinfunction "1_1") (pintype "passive"))
    )
    (net (code "70") (name "Net-(DD17-RBIAS)") (class "Default")
      (node (ref "DD17") (pin "24") (pinfunction "RBIAS_24") (pintype "passive"))
      (node (ref "R164") (pin "2") (pinfunction "2_2") (pintype "passive"))
    )
    (net (code "71") (name "Net-(DD17-SMBCLK)") (class "Default")
      (node (ref "DD17") (pin "14") (pinfunction "SMBCLK_14") (pintype "passive"))
      (node (ref "R166") (pin "2") (pinfunction "2_2") (pintype "passive"))
    )
    (net (code "72") (name "Net-(DD17-SMBDATA)") (class "Default")
      (node (ref "DD17") (pin "13") (pinfunction "SMBDATA_13") (pintype "passive"))
      (node (ref "R167") (pin "2") (pinfunction "2_2") (pintype "passive"))
    )
    (net (code "73") (name "Net-(DD17-SUSP_IND)") (class "Default")
      (node (ref "DD17") (pin "17") (pinfunction "SUSP_IND_17") (pintype "passive"))
      (node (ref "R165") (pin "1") (pinfunction "1_1") (pintype "passive"))
    )
    (net (code "74") (name "Net-(R175-Pad1)") (class "Default")
      (node (ref "R175") (pin "1") (pinfunction "1_1") (pintype "passive"))
      (node (ref "R176") (pin "2") (pinfunction "2_2") (pintype "passive"))
    )
    (net (code "75") (name "Net-(R176-Pad1)") (class "Default")
      (node (ref "R176") (pin "1") (pinfunction "1_1") (pintype "passive"))
      (node (ref "R177") (pin "2") (pinfunction "2_2") (pintype "passive"))
    )
    (net (code "76") (name "Net-(VD3-GND)") (class "Default")
      (node (ref "C349") (pin "1") (pinfunction "1_1") (pintype "passive"))
      (node (ref "C352") (pin "1") (pinfunction "1_1") (pintype "passive"))
      (node (ref "C357") (pin "2") (pinfunction "2_2") (pintype "passive"))
      (node (ref "C358") (pin "1") (pinfunction "1_1") (pintype "passive"))
      (node (ref "DD15") (pin "2") (pinfunction "GND1_2") (pintype "passive"))
      (node (ref "DD15") (pin "8") (pinfunction "GND1_8") (pintype "passive"))
      (node (ref "R175") (pin "2") (pinfunction "2_2") (pintype "passive"))
      (node (ref "R178") (pin "2") (pinfunction "2_2") (pintype "passive"))
      (node (ref "VD3") (pin "5") (pinfunction "GND_5") (pintype "passive"))
      (node (ref "VU3") (pin "2") (pinfunction "K_2") (pintype "passive"))
      (node (ref "XS2") (pin "4") (pinfunction "4_4") (pintype "passive"))
    )
    (net (code "77") (name "Net-(VU3-A)") (class "Default")
      (node (ref "R169") (pin "2") (pinfunction "2_2") (pintype "passive"))
      (node (ref "VU3") (pin "1") (pinfunction "A_1") (pintype "passive"))
    )
    (net (code "78") (name "REGV") (class "Default")
      (node (ref "C251") (pin "2") (pinfunction "2_2") (pintype "passive"))
      (node (ref "DD16") (pin "8") (pinfunction "DREG33_8") (pintype "passive"))
      (node (ref "R10") (pin "2") (pinfunction "2_2") (pintype "passive"))
    )
    (net (code "79") (name "RHP") (class "Default")
      (node (ref "C355") (pin "1") (pinfunction "1_1") (pintype "passive"))
      (node (ref "Z4") (pin "3") (pintype "passive"))
    )
    (net (code "80") (name "RMICN") (class "Default")
      (node (ref "C345") (pin "1") (pinfunction "1_1") (pintype "passive"))
      (node (ref "R173") (pin "2") (pinfunction "2_2") (pintype "passive"))
      (node (ref "Z5") (pin "4") (pintype "passive"))
    )
    (net (code "81") (name "RMICP") (class "Default")
      (node (ref "C344") (pin "1") (pinfunction "1_1") (pintype "passive"))
      (node (ref "R171") (pin "2") (pinfunction "2_2") (pintype "passive"))
      (node (ref "Z5") (pin "3") (pintype "passive"))
    )
    (net (code "82") (name "USBD1_N") (class "Default")
      (node (ref "DD13") (pin "5") (pinfunction "D–_5") (pintype "passive"))
      (node (ref "DD17") (pin "2") (pinfunction "USBDM_DN1_2") (pintype "passive"))
    )
    (net (code "83") (name "USBD1_P") (class "Default")
      (node (ref "DD13") (pin "4") (pinfunction "D+_4") (pintype "passive"))
      (node (ref "DD17") (pin "3") (pinfunction "USBDP_DN1_3") (pintype "passive"))
    )
    (net (code "84") (name "USBD2_N") (class "Default")
      (node (ref "DD16") (pin "44") (pinfunction "USBDM_44") (pintype "passive"))
      (node (ref "DD17") (pin "4") (pinfunction "USBDM_DN2_4") (pintype "passive"))
    )
    (net (code "85") (name "USBD2_P") (class "Default")
      (node (ref "DD16") (pin "43") (pinfunction "USBDP_43") (pintype "passive"))
      (node (ref "DD17") (pin "5") (pinfunction "USBDP_DN2_5") (pintype "passive"))
    )
    (net (code "86") (name "USBD_N") (class "Default")
      (node (ref "DD15") (pin "11") (pinfunction "DD-_11") (pintype "passive"))
      (node (ref "DD17") (pin "19") (pinfunction "USBDM_UP_19") (pintype "passive"))
    )
    (net (code "87") (name "USBD_P") (class "Default")
      (node (ref "DD15") (pin "10") (pinfunction "DD+_10") (pintype "passive"))
      (node (ref "DD17") (pin "20") (pinfunction "USBDP_UP_20") (pintype "passive"))
    )
    (net (code "88") (name "VBUS_ISO") (class "Default")
      (node (ref "DD13") (pin "8") (pinfunction "VBUS_8") (pintype "passive"))
      (node (ref "DD17") (pin "16") (pinfunction "VBUS_DET_16") (pintype "passive"))
      (node (ref "R168") (pin "2") (pinfunction "2_2") (pintype "passive"))
      (node (ref "VU3") (pin "3") (pinfunction "E_3") (pintype "passive"))
    )
    (net (code "89") (name "VDD_3V3") (class "Default")
      (node (ref "C111") (pin "2") (pinfunction "2_2") (pintype "passive"))
      (node (ref "C32") (pin "2") (pinfunction "2_2") (pintype "passive"))
      (node (ref "C38") (pin "2") (pinfunction "2_2") (pintype "passive"))
      (node (ref "C5") (pin "2") (pinfunction "2_2") (pintype "passive"))
      (node (ref "DD13") (pin "6") (pinfunction "VDD_6") (pintype "passive"))
      (node (ref "DD13") (pin "7") (pinfunction "REGIN_7") (pintype "passive"))
      (node (ref "DD17") (pin "1") (pinfunction "VDD33_1") (pintype "passive"))
      (node (ref "DD17") (pin "18") (pinfunction "VDD33_18") (pintype "passive"))
      (node (ref "DD17") (pin "9") (pinfunction "VDD33_9") (pintype "passive"))
      (node (ref "L60") (pin "1") (pinfunction "1_1") (pintype "passive"))
      (node (ref "R160") (pin "2") (pinfunction "2_2") (pintype "passive"))
      (node (ref "R162") (pin "2") (pinfunction "2_2") (pintype "passive"))
      (node (ref "R163") (pin "2") (pinfunction "2_2") (pintype "passive"))
      (node (ref "R165") (pin "2") (pinfunction "2_2") (pintype "passive"))
      (node (ref "R172") (pin "2") (pinfunction "2_2") (pintype "passive"))
    )
    (net (code "90") (name "VDD_5V0") (class "Default")
      (node (ref "L59") (pin "1") (pinfunction "1_1") (pintype "passive"))
      (node (ref "L62") (pin "1") (pinfunction "1_1") (pintype "passive"))
      (node (ref "R170") (pin "2") (pinfunction "2_2") (pintype "passive"))
    )
    (net (code "91") (name "unconnected-(DD13-CTS-Pad23)") (class "Default")
      (node (ref "DD13") (pin "23") (pinfunction "CTS_23") (pintype "passive"))
    )
    (net (code "92") (name "unconnected-(DD13-DCD-Pad1)") (class "Default")
      (node (ref "DD13") (pin "1") (pinfunction "DCD_1") (pintype "passive"))
    )
    (net (code "93") (name "unconnected-(DD13-DSR-Pad27)") (class "Default")
      (node (ref "DD13") (pin "27") (pinfunction "DSR_27") (pintype "passive"))
    )
    (net (code "94") (name "unconnected-(DD13-RI-Pad2)") (class "Default")
      (node (ref "DD13") (pin "2") (pinfunction "RI_2") (pintype "passive"))
    )
    (net (code "95") (name "unconnected-(DD13-SUSPEND-Pad12)") (class "Default")
      (node (ref "DD13") (pin "12") (pinfunction "SUSPEND_12") (pintype "passive"))
    )
    (net (code "96") (name "unconnected-(DD14-AUXOUT2-Pad22)") (class "Default")
      (node (ref "DD14") (pin "22") (pinfunction "AUXOUT2_22") (pintype "passive"))
    )
    (net (code "97") (name "unconnected-(DD14-CSB{slash}GPIO1-Pad15)") (class "Default")
      (node (ref "DD14") (pin "15") (pinfunction "CSB/GPIO1_15") (pintype "bidirectional"))
    )
    (net (code "98") (name "unconnected-(DD14-LLIN{slash}GPIO2-Pad3)") (class "Default")
      (node (ref "DD14") (pin "3") (pinfunction "LLIN/GPIO2_3") (pintype "passive"))
    )
    (net (code "99") (name "unconnected-(DD14-RLIN{slash}GPIO3-Pad6)") (class "Default")
      (node (ref "DD14") (pin "6") (pinfunction "RLIN/GPIO3_6") (pintype "passive"))
    )
    (net (code "100") (name "unconnected-(DD16-CS-Pad4)") (class "Default")
      (node (ref "DD16") (pin "4") (pinfunction "CS_4") (pintype "passive"))
    )
    (net (code "101") (name "unconnected-(DD16-DR-Pad1)") (class "Default")
      (node (ref "DD16") (pin "1") (pinfunction "DR_1") (pintype "passive"))
    )
    (net (code "102") (name "unconnected-(DD16-DW-Pad2)") (class "Default")
      (node (ref "DD16") (pin "2") (pinfunction "DW_2") (pintype "passive"))
    )
    (net (code "103") (name "unconnected-(DD16-LEDO-Pad11)") (class "Default")
      (node (ref "DD16") (pin "11") (pinfunction "LEDO_11") (pintype "passive"))
    )
    (net (code "104") (name "unconnected-(DD16-LEDR-Pad19)") (class "Default")
      (node (ref "DD16") (pin "19") (pinfunction "LEDR_19") (pintype "passive"))
    )
    (net (code "105") (name "unconnected-(DD16-MUTEP-Pad17)") (class "Default")
      (node (ref "DD16") (pin "17") (pinfunction "MUTEP_17") (pintype "passive"))
    )
    (net (code "106") (name "unconnected-(DD16-MUTER-Pad5)") (class "Default")
      (node (ref "DD16") (pin "5") (pinfunction "MUTER_5") (pintype "passive"))
    )
    (net (code "107") (name "unconnected-(DD16-PDSW-Pad42)") (class "Default")
      (node (ref "DD16") (pin "42") (pinfunction "PDSW_42") (pintype "passive"))
    )
    (net (code "108") (name "unconnected-(DD16-SK-Pad3)") (class "Default")
      (node (ref "DD16") (pin "3") (pinfunction "SK_3") (pintype "passive"))
    )
    (net (code "109") (name "unconnected-(DD16-VBIAS-Pad26)") (class "Default")
      (node (ref "DD16") (pin "26") (pinfunction "VBIAS_26") (pintype "passive"))
    )
    (net (code "110") (name "unconnected-(DD16-VOLDN-Pad47)") (class "Default")
      (node (ref "DD16") (pin "47") (pinfunction "VOLDN_47") (pintype "passive"))
    )
    (net (code "111") (name "unconnected-(DD16-VOLUP-Pad41)") (class "Default")
      (node (ref "DD16") (pin "41") (pinfunction "VOLUP_41") (pintype "passive"))
    )
    (net (code "112") (name "unconnected-(DD17-OCS1_N-Pad8)") (class "Default")
      (node (ref "DD17") (pin "8") (pinfunction "OCS1_N_8") (pintype "passive"))
    )
    (net (code "113") (name "unconnected-(DD17-OCS2_N-Pad12)") (class "Default")
      (node (ref "DD17") (pin "12") (pinfunction "OCS2_N_12") (pintype "passive"))
    )
    (net (code "114") (name "unconnected-(DD17-PLLFILT-Pad23)") (class "Default")
      (node (ref "DD17") (pin "23") (pinfunction "PLLFILT_23") (pintype "passive"))
    )
    (net (code "115") (name "unconnected-(DD17-PRTPWR1-Pad7)") (class "Default")
      (node (ref "DD17") (pin "7") (pinfunction "PRTPWR1_7") (pintype "passive"))
    )
    (net (code "116") (name "unconnected-(DD17-RESET_N-Pad15)") (class "Default")
      (node (ref "DD17") (pin "15") (pinfunction "RESET_N_15") (pintype "passive"))
    )
    (net (code "117") (name "unconnected-(VD3-ID-Pad4)") (class "Default")
      (node (ref "VD3") (pin "4") (pinfunction "ID_4") (pintype "passive"))
    )
    (net (code "118") (name "unconnected-(Z4-Pad1)") (class "Default")
      (node (ref "Z4") (pin "1") (pintype "passive"))
    )
    (net (code "119") (name "unconnected-(Z4-Pad2)") (class "Default")
      (node (ref "Z4") (pin "2") (pintype "passive"))
    )
    (net (code "120") (name "unconnected-(Z4-Pad7)") (class "Default")
      (node (ref "Z4") (pin "7") (pintype "passive"))
    )
    (net (code "121") (name "unconnected-(Z4-Pad8)") (class "Default")
      (node (ref "Z4") (pin "8") (pintype "passive"))
    )
  )
)
